# Sdcardreader.net
KiCad netlist of a schematic drawn in Altium Designer
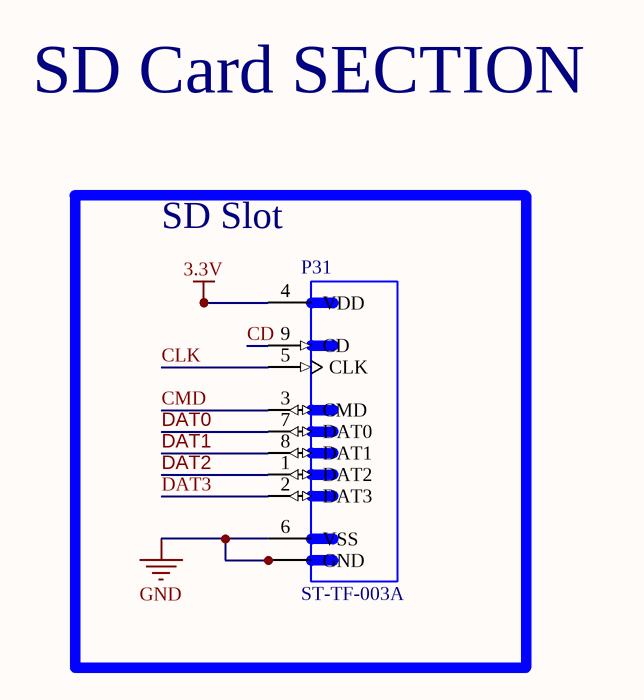
[diagram p0: Sdcardreader.SchDoc]

(export (version "E")
  (design (tool "Eeschema 10.0.6"))
  (components
    (comp (ref "P31")
      (value "ST-TF-003A")
      (footprint "SD CD")
      (description "Micro SD Card Socket")
      (libsource (lib "ST-TF-003A") (part "ST-TF-003A"))
    )
  )
  (nets
    (net (code "1") (name "/CD") (class "Default")
      (node (ref "P31") (pin "9") (pinfunction "CD_9") (pintype "input"))
    )
    (net (code "2") (name "/CLK") (class "Default")
      (node (ref "P31") (pin "5") (pinfunction "CLK_5") (pintype "input"))
    )
    (net (code "3") (name "/CMD") (class "Default")
      (node (ref "P31") (pin "3") (pinfunction "CMD_3") (pintype "bidirectional"))
    )
    (net (code "4") (name "/DAT0") (class "Default")
      (node (ref "P31") (pin "7") (pinfunction "DAT0_7") (pintype "bidirectional"))
    )
    (net (code "5") (name "/DAT1") (class "Default")
      (node (ref "P31") (pin "8") (pinfunction "DAT1_8") (pintype "bidirectional"))
    )
    (net (code "6") (name "/DAT2") (class "Default")
      (node (ref "P31") (pin "1") (pinfunction "DAT2_1") (pintype "bidirectional"))
    )
    (net (code "7") (name "/DAT3") (class "Default")
      (node (ref "P31") (pin "2") (pinfunction "DAT3_2") (pintype "bidirectional"))
    )
    (net (code "8") (name "3.3V") (class "Default")
      (node (ref "P31") (pin "4") (pinfunction "VDD_4") (pintype "power_in"))
    )
    (net (code "9") (name "GND") (class "Default")
      (node (ref "P31") (pin "6") (pinfunction "VSS_6") (pintype "passive"))
      (node (ref "P31") (pin "G1") (pinfunction "GND_G1") (pintype "passive"))
      (node (ref "P31") (pin "G2") (pinfunction "GND_G2") (pintype "passive"))
      (node (ref "P31") (pin "G3") (pinfunction "GND_G3") (pintype "passive"))
      (node (ref "P31") (pin "G4") (pinfunction "GND_G4") (pintype "passive"))
    )
  )
)
